# ADC_ASCII.net
KiCad netlist of a schematic drawn in Altium Designer
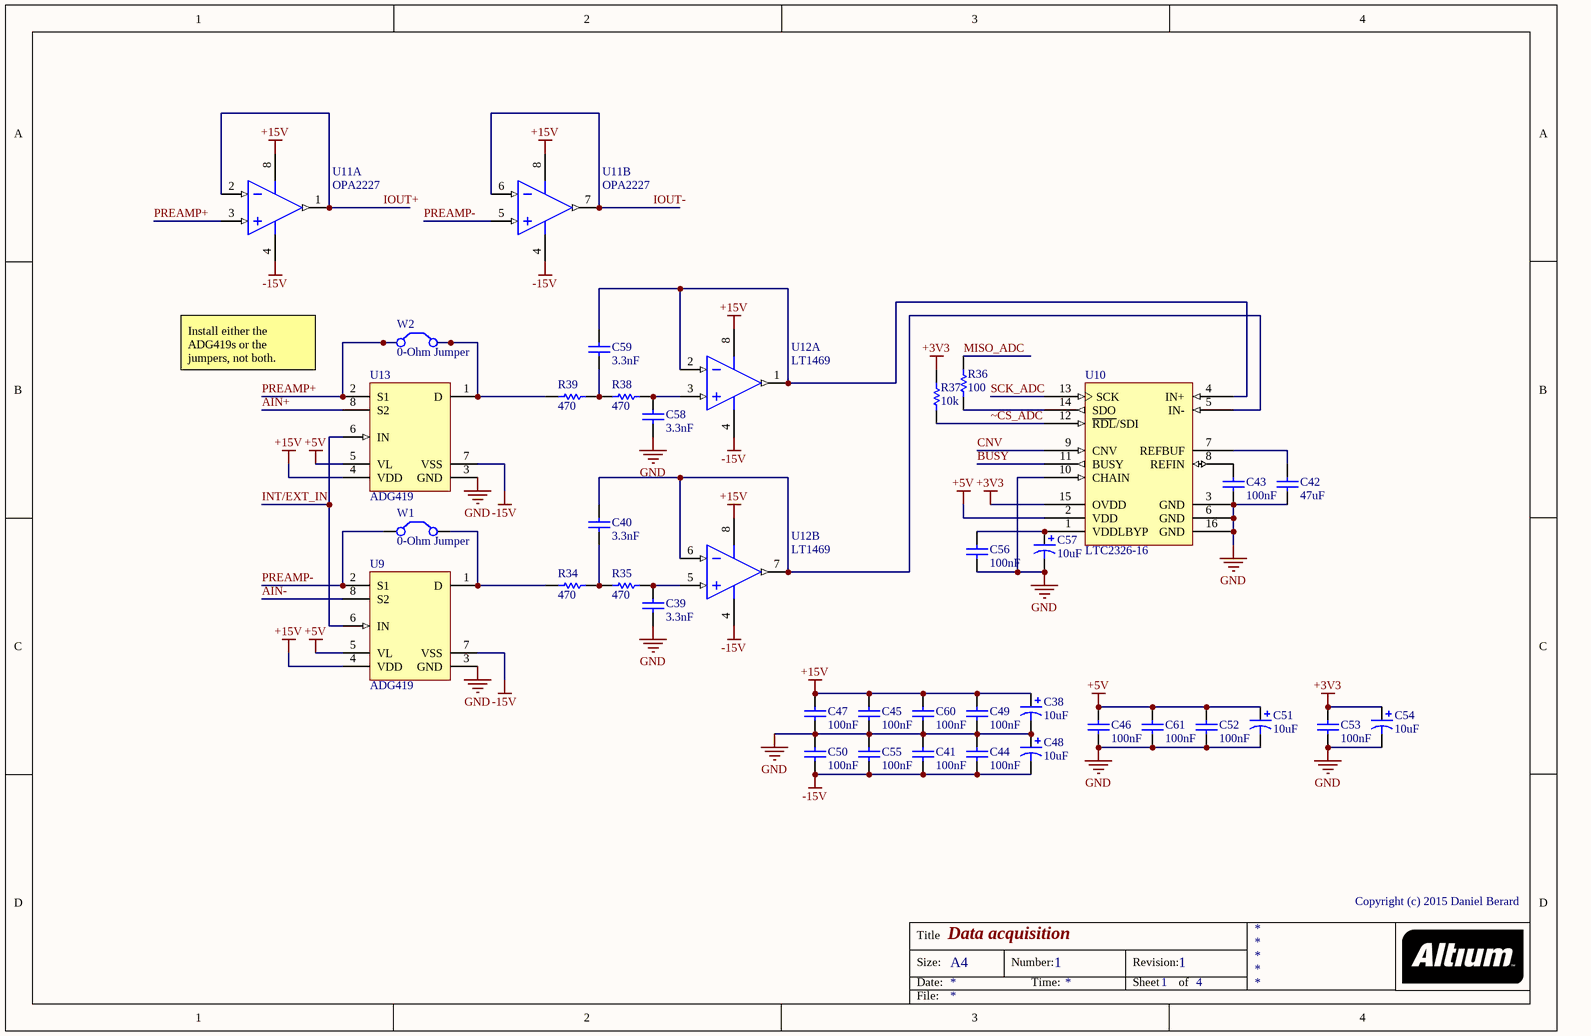
[diagram p0: ADC_ASCII.SchDoc]

(export (version "E")
  (design (tool "Eeschema 10.0.6"))
  (components
    (comp (ref "C38")
      (value "10uF")
      (footprint "3528")
      (description "Polarized Capacitor (Radial)")
      (fields (field (name "PUBLISHER") "Altium Limited"))
      (libsource (lib "Miscellaneous Devices") (part "Cap Pol1"))
    )
    (comp (ref "C39")
      (value "3.3nF")
      (footprint "6-0805_N")
      (description "Capacitor")
      (fields (field (name "PUBLISHER") "Altium Limited"))
      (libsource (lib "Miscellaneous Devices") (part "Cap"))
    )
    (comp (ref "C40")
      (value "3.3nF")
      (footprint "6-0805_N")
      (description "Capacitor")
      (fields (field (name "PUBLISHER") "Altium Limited"))
      (libsource (lib "Miscellaneous Devices") (part "Cap"))
    )
    (comp (ref "C41")
      (value "100nF")
      (footprint "6-0805_N")
      (description "Capacitor")
      (fields (field (name "PUBLISHER") "Altium Limited"))
      (libsource (lib "Miscellaneous Devices") (part "Cap"))
    )
    (comp (ref "C42")
      (value "47uF")
      (footprint "C1210")
      (description "Capacitor")
      (fields (field (name "PUBLISHER") "Altium Limited"))
      (libsource (lib "Miscellaneous Devices") (part "Cap"))
    )
    (comp (ref "C43")
      (value "100nF")
      (footprint "6-0805_N")
      (description "Capacitor")
      (fields (field (name "PUBLISHER") "Altium Limited"))
      (libsource (lib "Miscellaneous Devices") (part "Cap"))
    )
    (comp (ref "C44")
      (value "100nF")
      (footprint "6-0805_N")
      (description "Capacitor")
      (fields (field (name "PUBLISHER") "Altium Limited"))
      (libsource (lib "Miscellaneous Devices") (part "Cap"))
    )
    (comp (ref "C45")
      (value "100nF")
      (footprint "6-0805_N")
      (description "Capacitor")
      (fields (field (name "PUBLISHER") "Altium Limited"))
      (libsource (lib "Miscellaneous Devices") (part "Cap"))
    )
    (comp (ref "C46")
      (value "100nF")
      (footprint "6-0805_N")
      (description "Capacitor")
      (fields (field (name "PUBLISHER") "Altium Limited"))
      (libsource (lib "Miscellaneous Devices") (part "Cap"))
    )
    (comp (ref "C47")
      (value "100nF")
      (footprint "6-0805_N")
      (description "Capacitor")
      (fields (field (name "PUBLISHER") "Altium Limited"))
      (libsource (lib "Miscellaneous Devices") (part "Cap"))
    )
    (comp (ref "C48")
      (value "10uF")
      (footprint "3528")
      (description "Polarized Capacitor (Radial)")
      (fields (field (name "PUBLISHER") "Altium Limited"))
      (libsource (lib "Miscellaneous Devices") (part "Cap Pol1"))
    )
    (comp (ref "C49")
      (value "100nF")
      (footprint "6-0805_N")
      (description "Capacitor")
      (fields (field (name "PUBLISHER") "Altium Limited"))
      (libsource (lib "Miscellaneous Devices") (part "Cap"))
    )
    (comp (ref "C50")
      (value "100nF")
      (footprint "6-0805_N")
      (description "Capacitor")
      (fields (field (name "PUBLISHER") "Altium Limited"))
      (libsource (lib "Miscellaneous Devices") (part "Cap"))
    )
    (comp (ref "C51")
      (value "10uF")
      (footprint "6-0805_N")
      (description "Polarized Capacitor (Radial)")
      (fields (field (name "PUBLISHER") "Altium Limited"))
      (libsource (lib "Miscellaneous Devices") (part "Cap Pol1"))
    )
    (comp (ref "C52")
      (value "100nF")
      (footprint "6-0805_N")
      (description "Capacitor")
      (fields (field (name "PUBLISHER") "Altium Limited"))
      (libsource (lib "Miscellaneous Devices") (part "Cap"))
    )
    (comp (ref "C53")
      (value "100nF")
      (footprint "6-0805_N")
      (description "Capacitor")
      (fields (field (name "PUBLISHER") "Altium Limited"))
      (libsource (lib "Miscellaneous Devices") (part "Cap"))
    )
    (comp (ref "C54")
      (value "10uF")
      (footprint "6-0805_N")
      (description "Polarized Capacitor (Radial)")
      (fields (field (name "PUBLISHER") "Altium Limited"))
      (libsource (lib "Miscellaneous Devices") (part "Cap Pol1"))
    )
    (comp (ref "C55")
      (value "100nF")
      (footprint "6-0805_N")
      (description "Capacitor")
      (fields (field (name "PUBLISHER") "Altium Limited"))
      (libsource (lib "Miscellaneous Devices") (part "Cap"))
    )
    (comp (ref "C56")
      (value "100nF")
      (footprint "6-0805_N")
      (description "Capacitor")
      (fields (field (name "PUBLISHER") "Altium Limited"))
      (libsource (lib "Miscellaneous Devices") (part "Cap"))
    )
    (comp (ref "C57")
      (value "10uF")
      (footprint "6-0805_N")
      (description "Polarized Capacitor (Radial)")
      (fields (field (name "PUBLISHER") "Altium Limited"))
      (libsource (lib "Miscellaneous Devices") (part "Cap Pol1"))
    )
    (comp (ref "C58")
      (value "3.3nF")
      (footprint "6-0805_N")
      (description "Capacitor")
      (fields (field (name "PUBLISHER") "Altium Limited"))
      (libsource (lib "Miscellaneous Devices") (part "Cap"))
    )
    (comp (ref "C59")
      (value "3.3nF")
      (footprint "6-0805_N")
      (description "Capacitor")
      (fields (field (name "PUBLISHER") "Altium Limited"))
      (libsource (lib "Miscellaneous Devices") (part "Cap"))
    )
    (comp (ref "C60")
      (value "100nF")
      (footprint "6-0805_N")
      (description "Capacitor")
      (fields (field (name "PUBLISHER") "Altium Limited"))
      (libsource (lib "Miscellaneous Devices") (part "Cap"))
    )
    (comp (ref "C61")
      (value "100nF")
      (footprint "6-0805_N")
      (description "Capacitor")
      (fields (field (name "PUBLISHER") "Altium Limited"))
      (libsource (lib "Miscellaneous Devices") (part "Cap"))
    )
    (comp (ref "R34")
      (value "470")
      (footprint "6-0805_N")
      (description "Resistor")
      (fields (field (name "PUBLISHER") "Altium Limited"))
      (libsource (lib "Miscellaneous Devices") (part "Res1"))
    )
    (comp (ref "R35")
      (value "470")
      (footprint "6-0805_N")
      (description "Resistor")
      (fields (field (name "PUBLISHER") "Altium Limited"))
      (libsource (lib "Miscellaneous Devices") (part "Res1"))
    )
    (comp (ref "R36")
      (value "100")
      (footprint "6-0805_N")
      (description "Resistor")
      (fields (field (name "PUBLISHER") "Altium Limited"))
      (libsource (lib "Miscellaneous Devices") (part "Res1"))
    )
    (comp (ref "R37")
      (value "10k")
      (footprint "6-0805_N")
      (description "Resistor")
      (fields (field (name "PUBLISHER") "Altium Limited"))
      (libsource (lib "Miscellaneous Devices") (part "Res1"))
    )
    (comp (ref "R38")
      (value "470")
      (footprint "6-0805_N")
      (description "Resistor")
      (fields (field (name "PUBLISHER") "Altium Limited"))
      (libsource (lib "Miscellaneous Devices") (part "Res1"))
    )
    (comp (ref "R39")
      (value "470")
      (footprint "6-0805_N")
      (description "Resistor")
      (fields (field (name "PUBLISHER") "Altium Limited"))
      (libsource (lib "Miscellaneous Devices") (part "Res1"))
    )
    (comp (ref "U9")
      (value "ADG419")
      (footprint "ADI-RM-8_N")
      (description "LC2MOS Precision Mini-DIP Analog Switches, 25 Ohm Ron, 8-pin SOP (RM-8), Tube")
      (fields (field (name "MANUFACTURER") "Analog Devices") (field (name "PARTNUMBER") "ADG419BRMZ"))
      (libsource (lib "Altium Content Vault") (part "CMP-0792-00196-1"))
    )
    (comp (ref "U10") (value "LTC2326-16") (footprint "MSOP-16") (libsource (lib "DB") (part "LTC2326-16")))
    (comp (ref "U11")
      (value "OPA2227")
      (footprint "TI-D8_N")
      (fields (field (name "MANUFACTURER") "Texas Instruments") (field (name "PARTNUMBER") "OPA2227U/2K5"))
      (libsource (lib "Altium Content Vault") (part "CMP-0272-00267-2"))
    )
    (comp (ref "U12")
      (value "LT1469")
      (footprint "LT-S8-8_N")
      (fields
        (field (name "LINEAR TECHNOLOGY PART NUMBER") "LT1469-2")
        (field (name "PARTNUMBER") "LT1469CS8-2#PBF")
        (field (name "MANUFACTURER") "Linear Technology")
      )
      (libsource (lib "Altium Content Vault") (part "CMP-0359-02956-2"))
    )
    (comp (ref "U13")
      (value "ADG419")
      (footprint "ADI-RM-8_N")
      (description "LC2MOS Precision Mini-DIP Analog Switches, 25 Ohm Ron, 8-pin SOP (RM-8), Tube")
      (fields (field (name "MANUFACTURER") "Analog Devices") (field (name "PARTNUMBER") "ADG419BRMZ"))
      (libsource (lib "Altium Content Vault") (part "CMP-0792-00196-1"))
    )
    (comp (ref "W1")
      (value "0-Ohm Jumper")
      (footprint "6-0805_N")
      (description "Jumper Wire")
      (fields (field (name "PUBLISHER") "Altium Limited"))
      (libsource (lib "Miscellaneous Devices") (part "Jumper"))
    )
    (comp (ref "W2")
      (value "0-Ohm Jumper")
      (footprint "6-0805_N")
      (description "Jumper Wire")
      (fields (field (name "PUBLISHER") "Altium Limited"))
      (libsource (lib "Miscellaneous Devices") (part "Jumper"))
    )
  )
  (nets
    (net (code "1") (name "+3V3") (class "Default")
      (node (ref "C53") (pin "2") (pinfunction "2_2") (pintype "passive"))
      (node (ref "C54") (pin "1") (pinfunction "1_1") (pintype "passive"))
      (node (ref "R37") (pin "2") (pinfunction "2_2") (pintype "passive"))
      (node (ref "U10") (pin "15") (pinfunction "OVDD_15") (pintype "power_in"))
    )
    (net (code "2") (name "+5V") (class "Default")
      (node (ref "C46") (pin "2") (pinfunction "2_2") (pintype "passive"))
      (node (ref "C51") (pin "1") (pinfunction "1_1") (pintype "passive"))
      (node (ref "C52") (pin "2") (pinfunction "2_2") (pintype "passive"))
      (node (ref "C61") (pin "2") (pinfunction "2_2") (pintype "passive"))
      (node (ref "U10") (pin "2") (pinfunction "VDD_2") (pintype "power_in"))
      (node (ref "U13") (pin "5") (pinfunction "VL_5") (pintype "power_in"))
      (node (ref "U9") (pin "5") (pinfunction "VL_5") (pintype "power_in"))
    )
    (net (code "3") (name "+15V") (class "Default")
      (node (ref "C38") (pin "1") (pinfunction "1_1") (pintype "passive"))
      (node (ref "C45") (pin "2") (pinfunction "2_2") (pintype "passive"))
      (node (ref "C47") (pin "2") (pinfunction "2_2") (pintype "passive"))
      (node (ref "C49") (pin "2") (pinfunction "2_2") (pintype "passive"))
      (node (ref "C60") (pin "2") (pinfunction "2_2") (pintype "passive"))
      (node (ref "U11") (pin "8") (pinfunction "V+_8") (pintype "power_in"))
      (node (ref "U12") (pin "8") (pinfunction "V+_8") (pintype "power_in"))
      (node (ref "U13") (pin "4") (pinfunction "VDD_4") (pintype "power_in"))
      (node (ref "U9") (pin "4") (pinfunction "VDD_4") (pintype "power_in"))
    )
    (net (code "4") (name "-15V") (class "Default")
      (node (ref "C41") (pin "1") (pinfunction "1_1") (pintype "passive"))
      (node (ref "C44") (pin "1") (pinfunction "1_1") (pintype "passive"))
      (node (ref "C48") (pin "2") (pinfunction "2_2") (pintype "passive"))
      (node (ref "C50") (pin "1") (pinfunction "1_1") (pintype "passive"))
      (node (ref "C55") (pin "1") (pinfunction "1_1") (pintype "passive"))
      (node (ref "U11") (pin "4") (pinfunction "V-_4") (pintype "power_in"))
      (node (ref "U12") (pin "4") (pinfunction "V-_4") (pintype "power_in"))
      (node (ref "U13") (pin "7") (pinfunction "VSS_7") (pintype "power_in"))
      (node (ref "U9") (pin "7") (pinfunction "VSS_7") (pintype "power_in"))
    )
    (net (code "5") (name "/AIN+") (class "Default")
      (node (ref "U13") (pin "8") (pinfunction "S2_8") (pintype "passive"))
    )
    (net (code "6") (name "/AIN-") (class "Default")
      (node (ref "U9") (pin "8") (pinfunction "S2_8") (pintype "passive"))
    )
    (net (code "7") (name "/BUSY") (class "Default")
      (node (ref "U10") (pin "11") (pinfunction "BUSY_11") (pintype "output"))
    )
    (net (code "8") (name "/CNV") (class "Default")
      (node (ref "U10") (pin "9") (pinfunction "CNV_9") (pintype "input"))
    )
    (net (code "9") (name "/INT{slash}EXT_IN") (class "Default")
      (node (ref "U13") (pin "6") (pinfunction "IN_6") (pintype "input"))
      (node (ref "U9") (pin "6") (pinfunction "IN_6") (pintype "input"))
    )
    (net (code "10") (name "/IOUT+") (class "Default")
      (node (ref "U11") (pin "1") (pinfunction "OUT_A_1") (pintype "output"))
      (node (ref "U11") (pin "2") (pinfunction "IN_A-_2") (pintype "input"))
    )
    (net (code "11") (name "/IOUT-") (class "Default")
      (node (ref "U11") (pin "6") (pinfunction "IN_B-_6") (pintype "input"))
      (node (ref "U11") (pin "7") (pinfunction "OUT_B_7") (pintype "output"))
    )
    (net (code "12") (name "/MISO_ADC") (class "Default")
      (node (ref "R36") (pin "1") (pinfunction "1_1") (pintype "passive"))
    )
    (net (code "13") (name "/PREAMP+") (class "Default")
      (node (ref "U11") (pin "3") (pinfunction "IN_A+_3") (pintype "input"))
      (node (ref "U13") (pin "2") (pinfunction "S1_2") (pintype "passive"))
      (node (ref "W2") (pin "1") (pinfunction "C1_1") (pintype "passive"))
    )
    (net (code "14") (name "/PREAMP-") (class "Default")
      (node (ref "U11") (pin "5") (pinfunction "IN_B+_5") (pintype "input"))
      (node (ref "U9") (pin "2") (pinfunction "S1_2") (pintype "passive"))
      (node (ref "W1") (pin "1") (pinfunction "C1_1") (pintype "passive"))
    )
    (net (code "15") (name "/SCK_ADC") (class "Default")
      (node (ref "U10") (pin "13") (pinfunction "SCK_13") (pintype "input"))
    )
    (net (code "16") (name "/~CS_ADC") (class "Default")
      (node (ref "R37") (pin "1") (pinfunction "1_1") (pintype "passive"))
      (node (ref "U10") (pin "12") (pinfunction "~{RDL}/SDI_12") (pintype "input"))
    )
    (net (code "17") (name "GND") (class "Default")
      (node (ref "C38") (pin "2") (pinfunction "2_2") (pintype "passive"))
      (node (ref "C39") (pin "2") (pinfunction "2_2") (pintype "passive"))
      (node (ref "C41") (pin "2") (pinfunction "2_2") (pintype "passive"))
      (node (ref "C42") (pin "1") (pinfunction "1_1") (pintype "passive"))
      (node (ref "C43") (pin "1") (pinfunction "1_1") (pintype "passive"))
      (node (ref "C44") (pin "2") (pinfunction "2_2") (pintype "passive"))
      (node (ref "C45") (pin "1") (pinfunction "1_1") (pintype "passive"))
      (node (ref "C46") (pin "1") (pinfunction "1_1") (pintype "passive"))
      (node (ref "C47") (pin "1") (pinfunction "1_1") (pintype "passive"))
      (node (ref "C48") (pin "1") (pinfunction "1_1") (pintype "passive"))
      (node (ref "C49") (pin "1") (pinfunction "1_1") (pintype "passive"))
      (node (ref "C50") (pin "2") (pinfunction "2_2") (pintype "passive"))
      (node (ref "C51") (pin "2") (pinfunction "2_2") (pintype "passive"))
      (node (ref "C52") (pin "1") (pinfunction "1_1") (pintype "passive"))
      (node (ref "C53") (pin "1") (pinfunction "1_1") (pintype "passive"))
      (node (ref "C54") (pin "2") (pinfunction "2_2") (pintype "passive"))
      (node (ref "C55") (pin "2") (pinfunction "2_2") (pintype "passive"))
      (node (ref "C56") (pin "1") (pinfunction "1_1") (pintype "passive"))
      (node (ref "C57") (pin "2") (pinfunction "2_2") (pintype "passive"))
      (node (ref "C58") (pin "2") (pinfunction "2_2") (pintype "passive"))
      (node (ref "C60") (pin "1") (pinfunction "1_1") (pintype "passive"))
      (node (ref "C61") (pin "1") (pinfunction "1_1") (pintype "passive"))
      (node (ref "U10") (pin "10") (pinfunction "CHAIN_10") (pintype "input"))
      (node (ref "U10") (pin "16") (pinfunction "GND_16") (pintype "power_in"))
      (node (ref "U10") (pin "3") (pinfunction "GND_3") (pintype "power_in"))
      (node (ref "U10") (pin "6") (pinfunction "GND_6") (pintype "power_in"))
      (node (ref "U13") (pin "3") (pinfunction "GND_3") (pintype "power_in"))
      (node (ref "U9") (pin "3") (pinfunction "GND_3") (pintype "power_in"))
    )
    (net (code "18") (name "Net-(C40-Pad2)") (class "Default")
      (node (ref "C40") (pin "2") (pinfunction "2_2") (pintype "passive"))
      (node (ref "R34") (pin "2") (pinfunction "2_2") (pintype "passive"))
      (node (ref "R35") (pin "1") (pinfunction "1_1") (pintype "passive"))
    )
    (net (code "19") (name "Net-(C59-Pad2)") (class "Default")
      (node (ref "C59") (pin "2") (pinfunction "2_2") (pintype "passive"))
      (node (ref "R38") (pin "1") (pinfunction "1_1") (pintype "passive"))
      (node (ref "R39") (pin "2") (pinfunction "2_2") (pintype "passive"))
    )
    (net (code "20") (name "Net-(U9-D)") (class "Default")
      (node (ref "R34") (pin "1") (pinfunction "1_1") (pintype "passive"))
      (node (ref "U9") (pin "1") (pinfunction "D_1") (pintype "passive"))
      (node (ref "W1") (pin "2") (pinfunction "C2_2") (pintype "passive"))
    )
    (net (code "21") (name "Net-(U10-IN+)") (class "Default")
      (node (ref "C59") (pin "1") (pinfunction "1_1") (pintype "passive"))
      (node (ref "U10") (pin "4") (pinfunction "IN+_4") (pintype "input"))
      (node (ref "U12") (pin "1") (pinfunction "OUT_A_1") (pintype "output"))
      (node (ref "U12") (pin "2") (pinfunction "-IN_A_2") (pintype "input"))
    )
    (net (code "22") (name "Net-(U10-IN-)") (class "Default")
      (node (ref "C40") (pin "1") (pinfunction "1_1") (pintype "passive"))
      (node (ref "U10") (pin "5") (pinfunction "IN-_5") (pintype "input"))
      (node (ref "U12") (pin "6") (pinfunction "-IN_B_6") (pintype "input"))
      (node (ref "U12") (pin "7") (pinfunction "OUT_B_7") (pintype "output"))
    )
    (net (code "23") (name "Net-(U10-REFBUF)") (class "Default")
      (node (ref "C42") (pin "2") (pinfunction "2_2") (pintype "passive"))
      (node (ref "U10") (pin "7") (pinfunction "REFBUF_7") (pintype "passive"))
    )
    (net (code "24") (name "Net-(U10-REFIN)") (class "Default")
      (node (ref "C43") (pin "2") (pinfunction "2_2") (pintype "passive"))
      (node (ref "U10") (pin "8") (pinfunction "REFIN_8") (pintype "bidirectional"))
    )
    (net (code "25") (name "Net-(U10-SDO)") (class "Default")
      (node (ref "R36") (pin "2") (pinfunction "2_2") (pintype "passive"))
      (node (ref "U10") (pin "14") (pinfunction "SDO_14") (pintype "output"))
    )
    (net (code "26") (name "Net-(U10-VDDLBYP)") (class "Default")
      (node (ref "C56") (pin "2") (pinfunction "2_2") (pintype "passive"))
      (node (ref "C57") (pin "1") (pinfunction "1_1") (pintype "passive"))
      (node (ref "U10") (pin "1") (pinfunction "VDDLBYP_1") (pintype "passive"))
    )
    (net (code "27") (name "Net-(U12A-+IN_A)") (class "Default")
      (node (ref "C58") (pin "1") (pinfunction "1_1") (pintype "passive"))
      (node (ref "R38") (pin "2") (pinfunction "2_2") (pintype "passive"))
      (node (ref "U12") (pin "3") (pinfunction "+IN_A_3") (pintype "input"))
    )
    (net (code "28") (name "Net-(U12B-+IN_B)") (class "Default")
      (node (ref "C39") (pin "1") (pinfunction "1_1") (pintype "passive"))
      (node (ref "R35") (pin "2") (pinfunction "2_2") (pintype "passive"))
      (node (ref "U12") (pin "5") (pinfunction "+IN_B_5") (pintype "input"))
    )
    (net (code "29") (name "Net-(U13-D)") (class "Default")
      (node (ref "R39") (pin "1") (pinfunction "1_1") (pintype "passive"))
      (node (ref "U13") (pin "1") (pinfunction "D_1") (pintype "passive"))
      (node (ref "W2") (pin "2") (pinfunction "C2_2") (pintype "passive"))
    )
  )
)
